# nRF52810_qfaa.net
KiCad netlist of a schematic drawn in EAGLE
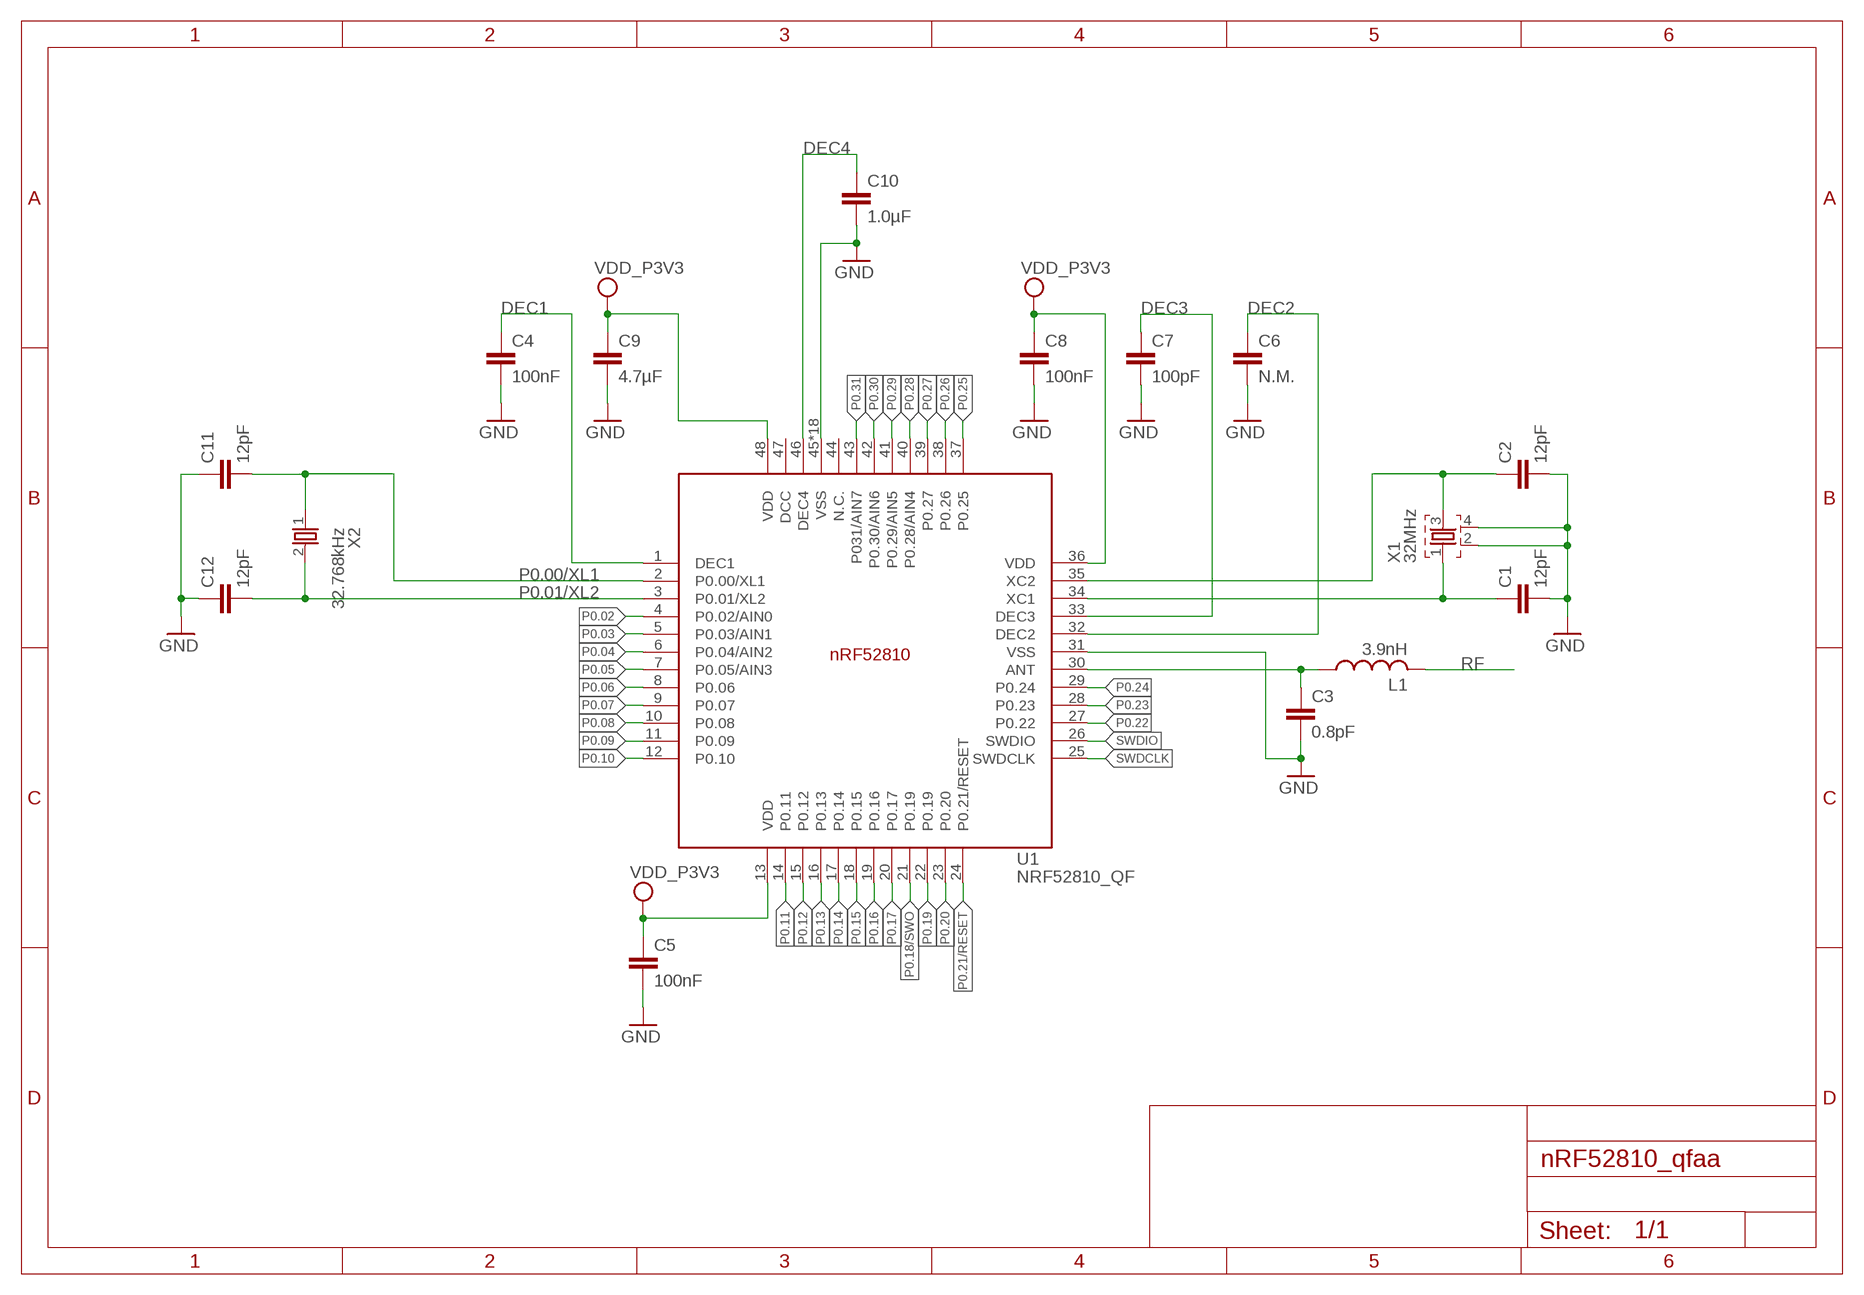
[diagram p0: schematic, sheet 1]

(export (version "E")
  (design (tool "Eeschema 10.0.6"))
  (components
    (comp (ref "C1")
      (value "12pF")
      (footprint "eagle-import:RESC0402_N")
      (libsource (lib "eagle-import") (part "CAPACITOR_0402_N"))
    )
    (comp (ref "C2")
      (value "12pF")
      (footprint "eagle-import:RESC0402_N")
      (libsource (lib "eagle-import") (part "CAPACITOR_0402_N"))
    )
    (comp (ref "C3")
      (value "0.8pF")
      (footprint "eagle-import:RESC0402_N")
      (libsource (lib "eagle-import") (part "CAPACITOR_0402_N"))
    )
    (comp (ref "C4")
      (value "100nF")
      (footprint "eagle-import:RESC0402_N")
      (libsource (lib "eagle-import") (part "CAPACITOR_0402_N"))
    )
    (comp (ref "C5")
      (value "100nF")
      (footprint "eagle-import:RESC0402_N")
      (libsource (lib "eagle-import") (part "CAPACITOR_0402_N"))
    )
    (comp (ref "C6")
      (value "N.M.")
      (footprint "eagle-import:RESC0402_N")
      (libsource (lib "eagle-import") (part "CAPACITOR_0402_N"))
    )
    (comp (ref "C7")
      (value "100pF")
      (footprint "eagle-import:RESC0402_N")
      (libsource (lib "eagle-import") (part "CAPACITOR_0402_N"))
    )
    (comp (ref "C8")
      (value "100nF")
      (footprint "eagle-import:RESC0402_N")
      (libsource (lib "eagle-import") (part "CAPACITOR_0402_N"))
    )
    (comp (ref "C9")
      (value "4.7µF")
      (footprint "eagle-import:RESC0603_N")
      (libsource (lib "eagle-import") (part "CAPACITOR_0603_N"))
    )
    (comp (ref "C10")
      (value "1.0µF")
      (footprint "eagle-import:RESC0603_N")
      (libsource (lib "eagle-import") (part "CAPACITOR_0603_N"))
    )
    (comp (ref "C11")
      (value "12pF")
      (footprint "eagle-import:RESC0402_N")
      (libsource (lib "eagle-import") (part "CAPACITOR_0402_N"))
    )
    (comp (ref "C12")
      (value "12pF")
      (footprint "eagle-import:RESC0402_N")
      (libsource (lib "eagle-import") (part "CAPACITOR_0402_N"))
    )
    (comp (ref "L1")
      (value "3.9nH")
      (footprint "eagle-import:RESC0402_N")
      (libsource (lib "eagle-import") (part "INDUCTOR_0402_N"))
    )
    (comp (ref "U1")
      (value "NRF52810_QF")
      (footprint "eagle-import:QFN40P600X600X90-48_N")
      (libsource (lib "eagle-import") (part "NRF52810_QF"))
    )
    (comp (ref "X1")
      (value "32MHz")
      (footprint "eagle-import:BT-XTAL_2016_N")
      (libsource (lib "eagle-import") (part "XTAL_32MHZ"))
    )
    (comp (ref "X2")
      (value "32.768kHz")
      (footprint "eagle-import:XTAL_3215_N")
      (libsource (lib "eagle-import") (part "XTAL_32KHZ"))
    )
  )
  (nets
    (net (code "1") (name "/DEC1") (class "Default")
      (node (ref "C4") (pin "1") (pinfunction "1_1") (pintype "passive"))
      (node (ref "U1") (pin "1") (pinfunction "DEC1_1") (pintype "bidirectional"))
    )
    (net (code "2") (name "/DEC2") (class "Default")
      (node (ref "C6") (pin "1") (pinfunction "1_1") (pintype "passive"))
      (node (ref "U1") (pin "32") (pinfunction "DEC2_32") (pintype "bidirectional"))
    )
    (net (code "3") (name "/DEC3") (class "Default")
      (node (ref "C7") (pin "1") (pinfunction "1_1") (pintype "passive"))
      (node (ref "U1") (pin "33") (pinfunction "DEC3_33") (pintype "bidirectional"))
    )
    (net (code "4") (name "/DEC4") (class "Default")
      (node (ref "C10") (pin "1") (pinfunction "1_1") (pintype "passive"))
      (node (ref "U1") (pin "46") (pinfunction "DEC4_46") (pintype "bidirectional"))
    )
    (net (code "5") (name "/P0.00{slash}XL1") (class "Default")
      (node (ref "C11") (pin "2") (pinfunction "2_2") (pintype "passive"))
      (node (ref "U1") (pin "2") (pinfunction "P0.00/XL1_2") (pintype "bidirectional"))
      (node (ref "X2") (pin "1") (pinfunction "1_1") (pintype "passive"))
    )
    (net (code "6") (name "/P0.01{slash}XL2") (class "Default")
      (node (ref "C12") (pin "2") (pinfunction "2_2") (pintype "passive"))
      (node (ref "U1") (pin "3") (pinfunction "P0.01/XL2_3") (pintype "bidirectional"))
      (node (ref "X2") (pin "2") (pinfunction "2_2") (pintype "passive"))
    )
    (net (code "7") (name "/RF") (class "Default")
      (node (ref "L1") (pin "2") (pinfunction "2_2") (pintype "passive"))
    )
    (net (code "8") (name "GND") (class "Default")
      (node (ref "C1") (pin "2") (pinfunction "2_2") (pintype "passive"))
      (node (ref "C10") (pin "2") (pinfunction "2_2") (pintype "passive"))
      (node (ref "C11") (pin "1") (pinfunction "1_1") (pintype "passive"))
      (node (ref "C12") (pin "1") (pinfunction "1_1") (pintype "passive"))
      (node (ref "C2") (pin "2") (pinfunction "2_2") (pintype "passive"))
      (node (ref "C3") (pin "2") (pinfunction "2_2") (pintype "passive"))
      (node (ref "C4") (pin "2") (pinfunction "2_2") (pintype "passive"))
      (node (ref "C5") (pin "2") (pinfunction "2_2") (pintype "passive"))
      (node (ref "C6") (pin "2") (pinfunction "2_2") (pintype "passive"))
      (node (ref "C7") (pin "2") (pinfunction "2_2") (pintype "passive"))
      (node (ref "C8") (pin "2") (pinfunction "2_2") (pintype "passive"))
      (node (ref "C9") (pin "2") (pinfunction "2_2") (pintype "passive"))
      (node (ref "U1") (pin "31") (pinfunction "VSS_31") (pintype "bidirectional"))
      (node (ref "U1") (pin "45") (pinfunction "VSS_45") (pintype "bidirectional"))
      (node (ref "U1") (pin "PAD") (pinfunction "VSS_PAD") (pintype "bidirectional"))
      (node (ref "U1") (pin "PAD@VIA01") (pinfunction "VSS_PAD@VIA01") (pintype "bidirectional"))
      (node (ref "U1") (pin "PAD@VIA02") (pinfunction "VSS_PAD@VIA02") (pintype "bidirectional"))
      (node (ref "U1") (pin "PAD@VIA03") (pinfunction "VSS_PAD@VIA03") (pintype "bidirectional"))
      (node (ref "U1") (pin "PAD@VIA04") (pinfunction "VSS_PAD@VIA04") (pintype "bidirectional"))
      (node (ref "U1") (pin "PAD@VIA05") (pinfunction "VSS_PAD@VIA05") (pintype "bidirectional"))
      (node (ref "U1") (pin "PAD@VIA06") (pinfunction "VSS_PAD@VIA06") (pintype "bidirectional"))
      (node (ref "U1") (pin "PAD@VIA07") (pinfunction "VSS_PAD@VIA07") (pintype "bidirectional"))
      (node (ref "U1") (pin "PAD@VIA08") (pinfunction "VSS_PAD@VIA08") (pintype "bidirectional"))
      (node (ref "U1") (pin "PAD@VIA09") (pinfunction "VSS_PAD@VIA09") (pintype "bidirectional"))
      (node (ref "U1") (pin "PAD@VIA10") (pinfunction "VSS_PAD@VIA10") (pintype "bidirectional"))
      (node (ref "U1") (pin "PAD@VIA11") (pinfunction "VSS_PAD@VIA11") (pintype "bidirectional"))
      (node (ref "U1") (pin "PAD@VIA12") (pinfunction "VSS_PAD@VIA12") (pintype "bidirectional"))
      (node (ref "U1") (pin "PAD@VIA13") (pinfunction "VSS_PAD@VIA13") (pintype "bidirectional"))
      (node (ref "U1") (pin "PAD@VIA14") (pinfunction "VSS_PAD@VIA14") (pintype "bidirectional"))
      (node (ref "U1") (pin "PAD@VIA15") (pinfunction "VSS_PAD@VIA15") (pintype "bidirectional"))
      (node (ref "U1") (pin "PAD@VIA16") (pinfunction "VSS_PAD@VIA16") (pintype "bidirectional"))
      (node (ref "X1") (pin "2") (pinfunction "2_2") (pintype "passive"))
      (node (ref "X1") (pin "4") (pinfunction "4_4") (pintype "passive"))
    )
    (net (code "9") (name "Net-(U1-ANT)") (class "Default")
      (node (ref "C3") (pin "1") (pinfunction "1_1") (pintype "passive"))
      (node (ref "L1") (pin "1") (pinfunction "1_1") (pintype "passive"))
      (node (ref "U1") (pin "30") (pinfunction "ANT_30") (pintype "bidirectional"))
    )
    (net (code "10") (name "Net-(U1-XC1)") (class "Default")
      (node (ref "C1") (pin "1") (pinfunction "1_1") (pintype "passive"))
      (node (ref "U1") (pin "34") (pinfunction "XC1_34") (pintype "bidirectional"))
      (node (ref "X1") (pin "1") (pinfunction "1_1") (pintype "passive"))
    )
    (net (code "11") (name "Net-(U1-XC2)") (class "Default")
      (node (ref "C2") (pin "1") (pinfunction "1_1") (pintype "passive"))
      (node (ref "U1") (pin "35") (pinfunction "XC2_35") (pintype "bidirectional"))
      (node (ref "X1") (pin "3") (pinfunction "3_3") (pintype "passive"))
    )
    (net (code "12") (name "P0.02") (class "Default")
      (node (ref "U1") (pin "4") (pinfunction "P0.02/AIN0_4") (pintype "bidirectional"))
    )
    (net (code "13") (name "P0.03") (class "Default")
      (node (ref "U1") (pin "5") (pinfunction "P0.03/AIN1_5") (pintype "bidirectional"))
    )
    (net (code "14") (name "P0.04") (class "Default")
      (node (ref "U1") (pin "6") (pinfunction "P0.04/AIN2_6") (pintype "bidirectional"))
    )
    (net (code "15") (name "P0.05") (class "Default")
      (node (ref "U1") (pin "7") (pinfunction "P0.05/AIN3_7") (pintype "bidirectional"))
    )
    (net (code "16") (name "P0.06") (class "Default")
      (node (ref "U1") (pin "8") (pinfunction "P0.06_8") (pintype "bidirectional"))
    )
    (net (code "17") (name "P0.07") (class "Default")
      (node (ref "U1") (pin "9") (pinfunction "P0.07_9") (pintype "bidirectional"))
    )
    (net (code "18") (name "P0.08") (class "Default")
      (node (ref "U1") (pin "10") (pinfunction "P0.08_10") (pintype "bidirectional"))
    )
    (net (code "19") (name "P0.09") (class "Default")
      (node (ref "U1") (pin "11") (pinfunction "P0.09_11") (pintype "bidirectional"))
    )
    (net (code "20") (name "P0.10") (class "Default")
      (node (ref "U1") (pin "12") (pinfunction "P0.10_12") (pintype "bidirectional"))
    )
    (net (code "21") (name "P0.11") (class "Default")
      (node (ref "U1") (pin "14") (pinfunction "P0.11_14") (pintype "bidirectional"))
    )
    (net (code "22") (name "P0.12") (class "Default")
      (node (ref "U1") (pin "15") (pinfunction "P0.12_15") (pintype "bidirectional"))
    )
    (net (code "23") (name "P0.13") (class "Default")
      (node (ref "U1") (pin "16") (pinfunction "P0.13_16") (pintype "bidirectional"))
    )
    (net (code "24") (name "P0.14") (class "Default")
      (node (ref "U1") (pin "17") (pinfunction "P0.14_17") (pintype "bidirectional"))
    )
    (net (code "25") (name "P0.15") (class "Default")
      (node (ref "U1") (pin "18") (pinfunction "P0.15_18") (pintype "bidirectional"))
    )
    (net (code "26") (name "P0.16") (class "Default")
      (node (ref "U1") (pin "19") (pinfunction "P0.16_19") (pintype "bidirectional"))
    )
    (net (code "27") (name "P0.17") (class "Default")
      (node (ref "U1") (pin "20") (pinfunction "P0.17_20") (pintype "bidirectional"))
    )
    (net (code "28") (name "P0.18{slash}SWO") (class "Default")
      (node (ref "U1") (pin "21") (pinfunction "P0.19_21") (pintype "bidirectional"))
    )
    (net (code "29") (name "P0.19") (class "Default")
      (node (ref "U1") (pin "22") (pinfunction "P0.19_22") (pintype "bidirectional"))
    )
    (net (code "30") (name "P0.20") (class "Default")
      (node (ref "U1") (pin "23") (pinfunction "P0.20_23") (pintype "bidirectional"))
    )
    (net (code "31") (name "P0.21{slash}RESET") (class "Default")
      (node (ref "U1") (pin "24") (pinfunction "P0.21/RESET_24") (pintype "bidirectional"))
    )
    (net (code "32") (name "P0.22") (class "Default")
      (node (ref "U1") (pin "27") (pinfunction "P0.22_27") (pintype "bidirectional"))
    )
    (net (code "33") (name "P0.23") (class "Default")
      (node (ref "U1") (pin "28") (pinfunction "P0.23_28") (pintype "bidirectional"))
    )
    (net (code "34") (name "P0.24") (class "Default")
      (node (ref "U1") (pin "29") (pinfunction "P0.24_29") (pintype "bidirectional"))
    )
    (net (code "35") (name "P0.25") (class "Default")
      (node (ref "U1") (pin "37") (pinfunction "P0.25_37") (pintype "bidirectional"))
    )
    (net (code "36") (name "P0.26") (class "Default")
      (node (ref "U1") (pin "38") (pinfunction "P0.26_38") (pintype "bidirectional"))
    )
    (net (code "37") (name "P0.27") (class "Default")
      (node (ref "U1") (pin "39") (pinfunction "P0.27_39") (pintype "bidirectional"))
    )
    (net (code "38") (name "P0.28") (class "Default")
      (node (ref "U1") (pin "40") (pinfunction "P0.28/AIN4_40") (pintype "bidirectional"))
    )
    (net (code "39") (name "P0.29") (class "Default")
      (node (ref "U1") (pin "41") (pinfunction "P0.29/AIN5_41") (pintype "bidirectional"))
    )
    (net (code "40") (name "P0.30") (class "Default")
      (node (ref "U1") (pin "42") (pinfunction "P0.30/AIN6_42") (pintype "bidirectional"))
    )
    (net (code "41") (name "P0.31") (class "Default")
      (node (ref "U1") (pin "43") (pinfunction "P031/AIN7_43") (pintype "bidirectional"))
    )
    (net (code "42") (name "SWDCLK") (class "Default")
      (node (ref "U1") (pin "25") (pinfunction "SWDCLK_25") (pintype "bidirectional"))
    )
    (net (code "43") (name "SWDIO") (class "Default")
      (node (ref "U1") (pin "26") (pinfunction "SWDIO_26") (pintype "bidirectional"))
    )
    (net (code "44") (name "VDD_P3V3") (class "Default")
      (node (ref "C5") (pin "1") (pinfunction "1_1") (pintype "passive"))
      (node (ref "C8") (pin "1") (pinfunction "1_1") (pintype "passive"))
      (node (ref "C9") (pin "1") (pinfunction "1_1") (pintype "passive"))
      (node (ref "U1") (pin "13") (pinfunction "VDD_13") (pintype "bidirectional"))
      (node (ref "U1") (pin "36") (pinfunction "VDD_36") (pintype "bidirectional"))
      (node (ref "U1") (pin "48") (pinfunction "VDD_48") (pintype "bidirectional"))
    )
    (net (code "45") (name "unconnected-(U1-DCC-Pad47)") (class "Default")
      (node (ref "U1") (pin "47") (pinfunction "DCC_47") (pintype "bidirectional"))
    )
    (net (code "46") (name "unconnected-(U1-N.C.-Pad44)") (class "Default")
      (node (ref "U1") (pin "44") (pinfunction "N.C._44") (pintype "bidirectional"))
    )
  )
)
